# Sheet1.net
KiCad netlist of a schematic drawn in Altium Designer
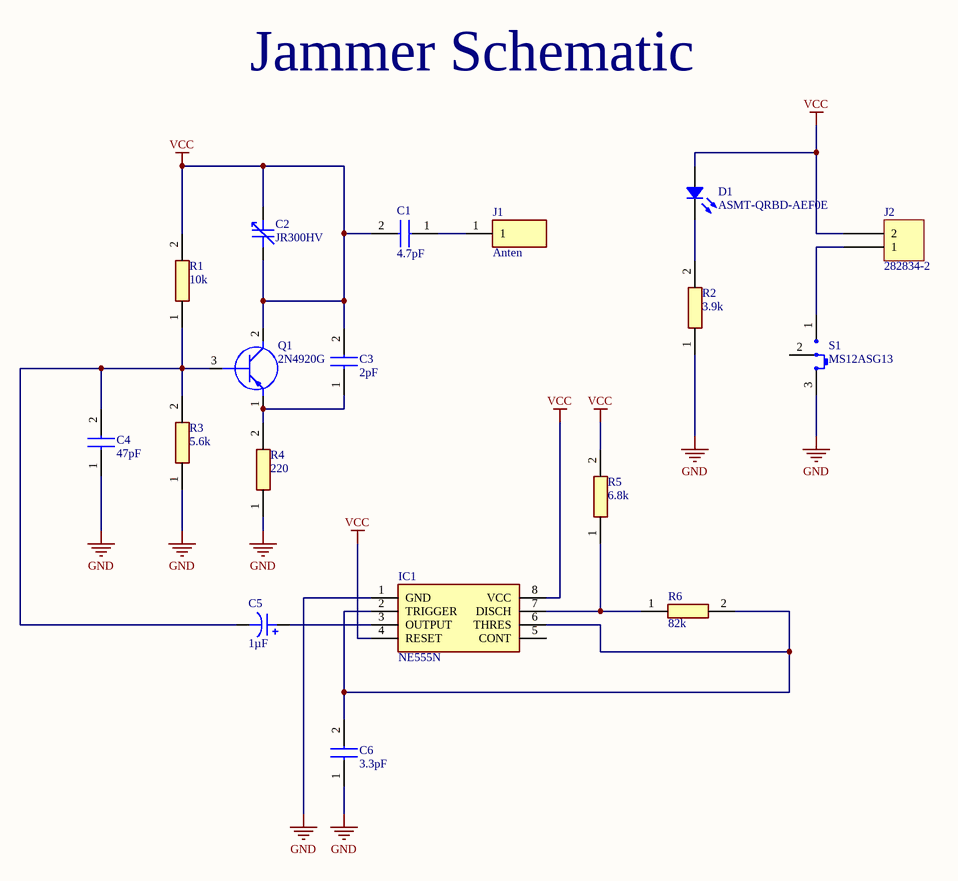
[diagram p0: Sheet1.SchDoc]

(export (version "E")
  (design (tool "Eeschema 10.0.6"))
  (components
    (comp (ref "C1")
      (value "4.7pF")
      (footprint "SamacSys:561R10TCCQ50")
      (description "Capacitor")
      (fields
        (field (name "MANUFACTURER_PART_NUMBER") "561R10TCCQ50")
        (field (name "MOUSER PART NUMBER") "75-561R10TCCQ50")
      )
      (libsource (lib "*") (part "561R10TCCQ50"))
    )
    (comp (ref "C2")
      (value "JR300HV")
      (footprint "KNOWLES JR")
      (description "CAP TRIMMER 5.5-30PF 350V SMD")
      (fields (field (name "MANUFACTURER") "Knowles Voltronics"))
      (libsource (lib "Celestial Altium Library - altium_library") (part "TRIMMER CAPACITOR"))
    )
    (comp (ref "C3")
      (value "2pF")
      (footprint "SamacSys:561R10TCCQ50")
      (description "Capacitor")
      (fields
        (field (name "MANUFACTURER_PART_NUMBER") "561R10TCCQ50")
        (field (name "MOUSER PART NUMBER") "75-561R10TCCQ50")
      )
      (libsource (lib "*") (part "561R10TCCQ50"))
    )
    (comp (ref "C4")
      (value "47pF")
      (footprint "SamacSys:561R10TCCQ50")
      (description "Capacitor")
      (fields
        (field (name "MANUFACTURER_PART_NUMBER") "561R10TCCQ50")
        (field (name "MOUSER PART NUMBER") "75-561R10TCCQ50")
      )
      (libsource (lib "*") (part "561R10TCCQ50"))
    )
    (comp (ref "C5")
      (value "1µF")
      (footprint "CAP TH ALUM ELEC D5.00mm S2.00mm H12.50mm")
      (description "CAP 1 UF 20% 63 V")
      (fields (field (name "PART NUMBER") "860010772005") (field (name "MANUFACTURER") "Würth Elektronik"))
      (libsource (lib "Celestial Altium Library - altium_library") (part "Polarised Capacitor"))
    )
    (comp (ref "C6")
      (value "3.3pF")
      (footprint "SamacSys:561R10TCCQ50")
      (description "Capacitor")
      (fields
        (field (name "MANUFACTURER_PART_NUMBER") "561R10TCCQ50")
        (field (name "MOUSER PART NUMBER") "75-561R10TCCQ50")
      )
      (libsource (lib "*") (part "561R10TCCQ50"))
    )
    (comp (ref "D1")
      (value "ASMT-QRBD-AEF0E")
      (footprint "Broadcom 4-PLLC 3228")
      (description "LED INDICATOR 0.5W RED 4PLCC")
      (fields (field (name "MANUFACTURER") "Broadcom Limited"))
      (libsource (lib "Celestial Altium Library - altium_library") (part "LED"))
    )
    (comp (ref "IC1")
      (value "NE555N")
      (footprint "SamacSys:DIP762W56P254L959H533Q8N")
      (description "Integrated Circuit")
      (libsource (lib "*") (part "NE555N"))
    )
    (comp (ref "J1")
      (value "Anten")
      (footprint "SamacSys:M3902958360")
      (description "Connector")
      (fields
        (field (name "MANUFACTURER_PART_NUMBER") "M39029/58-360")
        (field (name "MOUSER PART NUMBER") "571-M39029/58-360")
      )
      (libsource (lib "*") (part "M39029_58-360"))
    )
    (comp (ref "J2")
      (value "282834-2")
      (footprint "TE 282834-2")
      (description "TERM BLK 2P SIDE ENT 2.54MM PCB")
      (fields (field (name "MANUFACTURER") "TE Connectivity AMP Connectors") (field (name "VOLTAGE") "150V"))
      (libsource (lib "Celestial Altium Library - altium_library") (part "2 Pin"))
    )
    (comp (ref "Q1")
      (value "2N4920G")
      (footprint "SamacSys:TO229P300X760X1364-3P")
      (description "Transistor BJT PNP")
      (fields (field (name "MOUSER PART NUMBER") "863-2N4920G"))
      (libsource (lib "*") (part "2N4920G"))
    )
    (comp (ref "R1")
      (value "10k")
      (footprint "SamacSys:RESAD1987W56L1031D239")
      (description "Resistor")
      (fields
        (field (name "MANUFACTURER_PART_NUMBER") "RS01A1R000FE12")
        (field (name "MOUSER PART NUMBER") "71-RS01A1R000FE12")
      )
      (libsource (lib "") (part "RS01A1R000FE12_1"))
    )
    (comp (ref "R2")
      (value "3.9k")
      (footprint "SamacSys:RESAD1987W56L1031D239")
      (description "Resistor")
      (fields
        (field (name "MANUFACTURER_PART_NUMBER") "RS01A1R000FE12")
        (field (name "MOUSER PART NUMBER") "71-RS01A1R000FE12")
      )
      (libsource (lib "") (part "RS01A1R000FE12_1"))
    )
    (comp (ref "R3")
      (value "5.6k")
      (footprint "SamacSys:RESAD1987W56L1031D239")
      (description "Resistor")
      (fields
        (field (name "MANUFACTURER_PART_NUMBER") "RS01A1R000FE12")
        (field (name "MOUSER PART NUMBER") "71-RS01A1R000FE12")
      )
      (libsource (lib "") (part "RS01A1R000FE12_1"))
    )
    (comp (ref "R4")
      (value "220")
      (footprint "SamacSys:RESAD1987W56L1031D239")
      (description "Resistor")
      (fields
        (field (name "MANUFACTURER_PART_NUMBER") "RS01A1R000FE12")
        (field (name "MOUSER PART NUMBER") "71-RS01A1R000FE12")
      )
      (libsource (lib "") (part "RS01A1R000FE12_1"))
    )
    (comp (ref "R5")
      (value "6.8k")
      (footprint "SamacSys:RESAD1987W56L1031D239")
      (description "Resistor")
      (fields
        (field (name "MANUFACTURER_PART_NUMBER") "RS01A1R000FE12")
        (field (name "MOUSER PART NUMBER") "71-RS01A1R000FE12")
      )
      (libsource (lib "") (part "RS01A1R000FE12_1"))
    )
    (comp (ref "R6")
      (value "82k")
      (footprint "SamacSys:RESAD1987W56L1031D239")
      (description "Resistor")
      (fields
        (field (name "MANUFACTURER_PART_NUMBER") "RS01A1R000FE12")
        (field (name "MOUSER PART NUMBER") "71-RS01A1R000FE12")
      )
      (libsource (lib "*") (part "RS01A1R000FE12"))
    )
    (comp (ref "S1")
      (value "MS12ASG13")
      (footprint "NKK MS12ASG13")
      (description "SWITCH SLIDE SPDT 0.4VA 28V")
      (fields (field (name "MANUFACTURER") "NKK Switches"))
      (libsource (lib "Celestial Altium Library - altium_library") (part "NKK MS12ASG13"))
    )
  )
  (nets
    (net (code "1") (name "GND") (class "Default")
      (node (ref "C4") (pin "1") (pinfunction "1_1") (pintype "passive"))
      (node (ref "C6") (pin "1") (pinfunction "1_1") (pintype "passive"))
      (node (ref "IC1") (pin "1") (pinfunction "GND_1") (pintype "passive"))
      (node (ref "R2") (pin "1") (pinfunction "1_1") (pintype "passive"))
      (node (ref "R3") (pin "1") (pinfunction "1_1") (pintype "passive"))
      (node (ref "R4") (pin "1") (pinfunction "1_1") (pintype "passive"))
      (node (ref "S1") (pin "3") (pinfunction "3_3") (pintype "passive"))
    )
    (net (code "2") (name "Net-(C1-Pad1)") (class "Default")
      (node (ref "C1") (pin "1") (pinfunction "1_1") (pintype "passive"))
      (node (ref "J1") (pin "1") (pinfunction "1_1") (pintype "passive"))
    )
    (net (code "3") (name "Net-(D1-Pad2)") (class "Default")
      (node (ref "D1") (pin "2") (pinfunction "2_2") (pintype "passive"))
      (node (ref "R2") (pin "2") (pinfunction "2_2") (pintype "passive"))
    )
    (net (code "4") (name "Net-(IC1-DISCH)") (class "Default")
      (node (ref "IC1") (pin "7") (pinfunction "DISCH_7") (pintype "passive"))
      (node (ref "R5") (pin "1") (pinfunction "1_1") (pintype "passive"))
      (node (ref "R6") (pin "1") (pinfunction "1_1") (pintype "passive"))
    )
    (net (code "5") (name "Net-(IC1-OUTPUT)") (class "Default")
      (node (ref "C5") (pin "1") (pinfunction "1_1") (pintype "passive"))
      (node (ref "IC1") (pin "3") (pinfunction "OUTPUT_3") (pintype "passive"))
    )
    (net (code "6") (name "Net-(IC1-THRES)") (class "Default")
      (node (ref "C6") (pin "2") (pinfunction "2_2") (pintype "passive"))
      (node (ref "IC1") (pin "2") (pinfunction "TRIGGER_2") (pintype "passive"))
      (node (ref "IC1") (pin "6") (pinfunction "THRES_6") (pintype "passive"))
      (node (ref "R6") (pin "2") (pinfunction "2_2") (pintype "passive"))
    )
    (net (code "7") (name "Net-(J2-Pad1)") (class "Default")
      (node (ref "J2") (pin "1") (pinfunction "1_1") (pintype "passive"))
      (node (ref "S1") (pin "1") (pinfunction "1_1") (pintype "passive"))
    )
    (net (code "8") (name "Net-(Q1-B)") (class "Default")
      (node (ref "C4") (pin "2") (pinfunction "2_2") (pintype "passive"))
      (node (ref "C5") (pin "2") (pinfunction "2_2") (pintype "passive"))
      (node (ref "Q1") (pin "3") (pinfunction "B_3") (pintype "passive"))
      (node (ref "R1") (pin "1") (pinfunction "1_1") (pintype "passive"))
      (node (ref "R3") (pin "2") (pinfunction "2_2") (pintype "passive"))
    )
    (net (code "9") (name "Net-(Q1-E)") (class "Default")
      (node (ref "C3") (pin "1") (pinfunction "1_1") (pintype "passive"))
      (node (ref "Q1") (pin "1") (pinfunction "E_1") (pintype "passive"))
      (node (ref "R4") (pin "2") (pinfunction "2_2") (pintype "passive"))
    )
    (net (code "10") (name "VCC") (class "Default")
      (node (ref "C1") (pin "2") (pinfunction "2_2") (pintype "passive"))
      (node (ref "C2") (pin "1") (pinfunction "1_1") (pintype "passive"))
      (node (ref "C2") (pin "2") (pinfunction "2_2") (pintype "passive"))
      (node (ref "C3") (pin "2") (pinfunction "2_2") (pintype "passive"))
      (node (ref "D1") (pin "1") (pinfunction "1_1") (pintype "passive"))
      (node (ref "IC1") (pin "4") (pinfunction "RESET_4") (pintype "passive"))
      (node (ref "IC1") (pin "8") (pinfunction "VCC_8") (pintype "passive"))
      (node (ref "J2") (pin "2") (pinfunction "2_2") (pintype "passive"))
      (node (ref "Q1") (pin "2") (pinfunction "C_2") (pintype "passive"))
      (node (ref "R1") (pin "2") (pinfunction "2_2") (pintype "passive"))
      (node (ref "R5") (pin "2") (pinfunction "2_2") (pintype "passive"))
    )
    (net (code "11") (name "unconnected-(IC1-CONT-Pad5)") (class "Default")
      (node (ref "IC1") (pin "5") (pinfunction "CONT_5") (pintype "passive"))
    )
    (net (code "12") (name "unconnected-(S1-COM-Pad2)") (class "Default")
      (node (ref "S1") (pin "2") (pinfunction "COM_2") (pintype "passive"))
    )
  )
)
